# openSX70-dongle.net
KiCad netlist of a schematic drawn in EAGLE
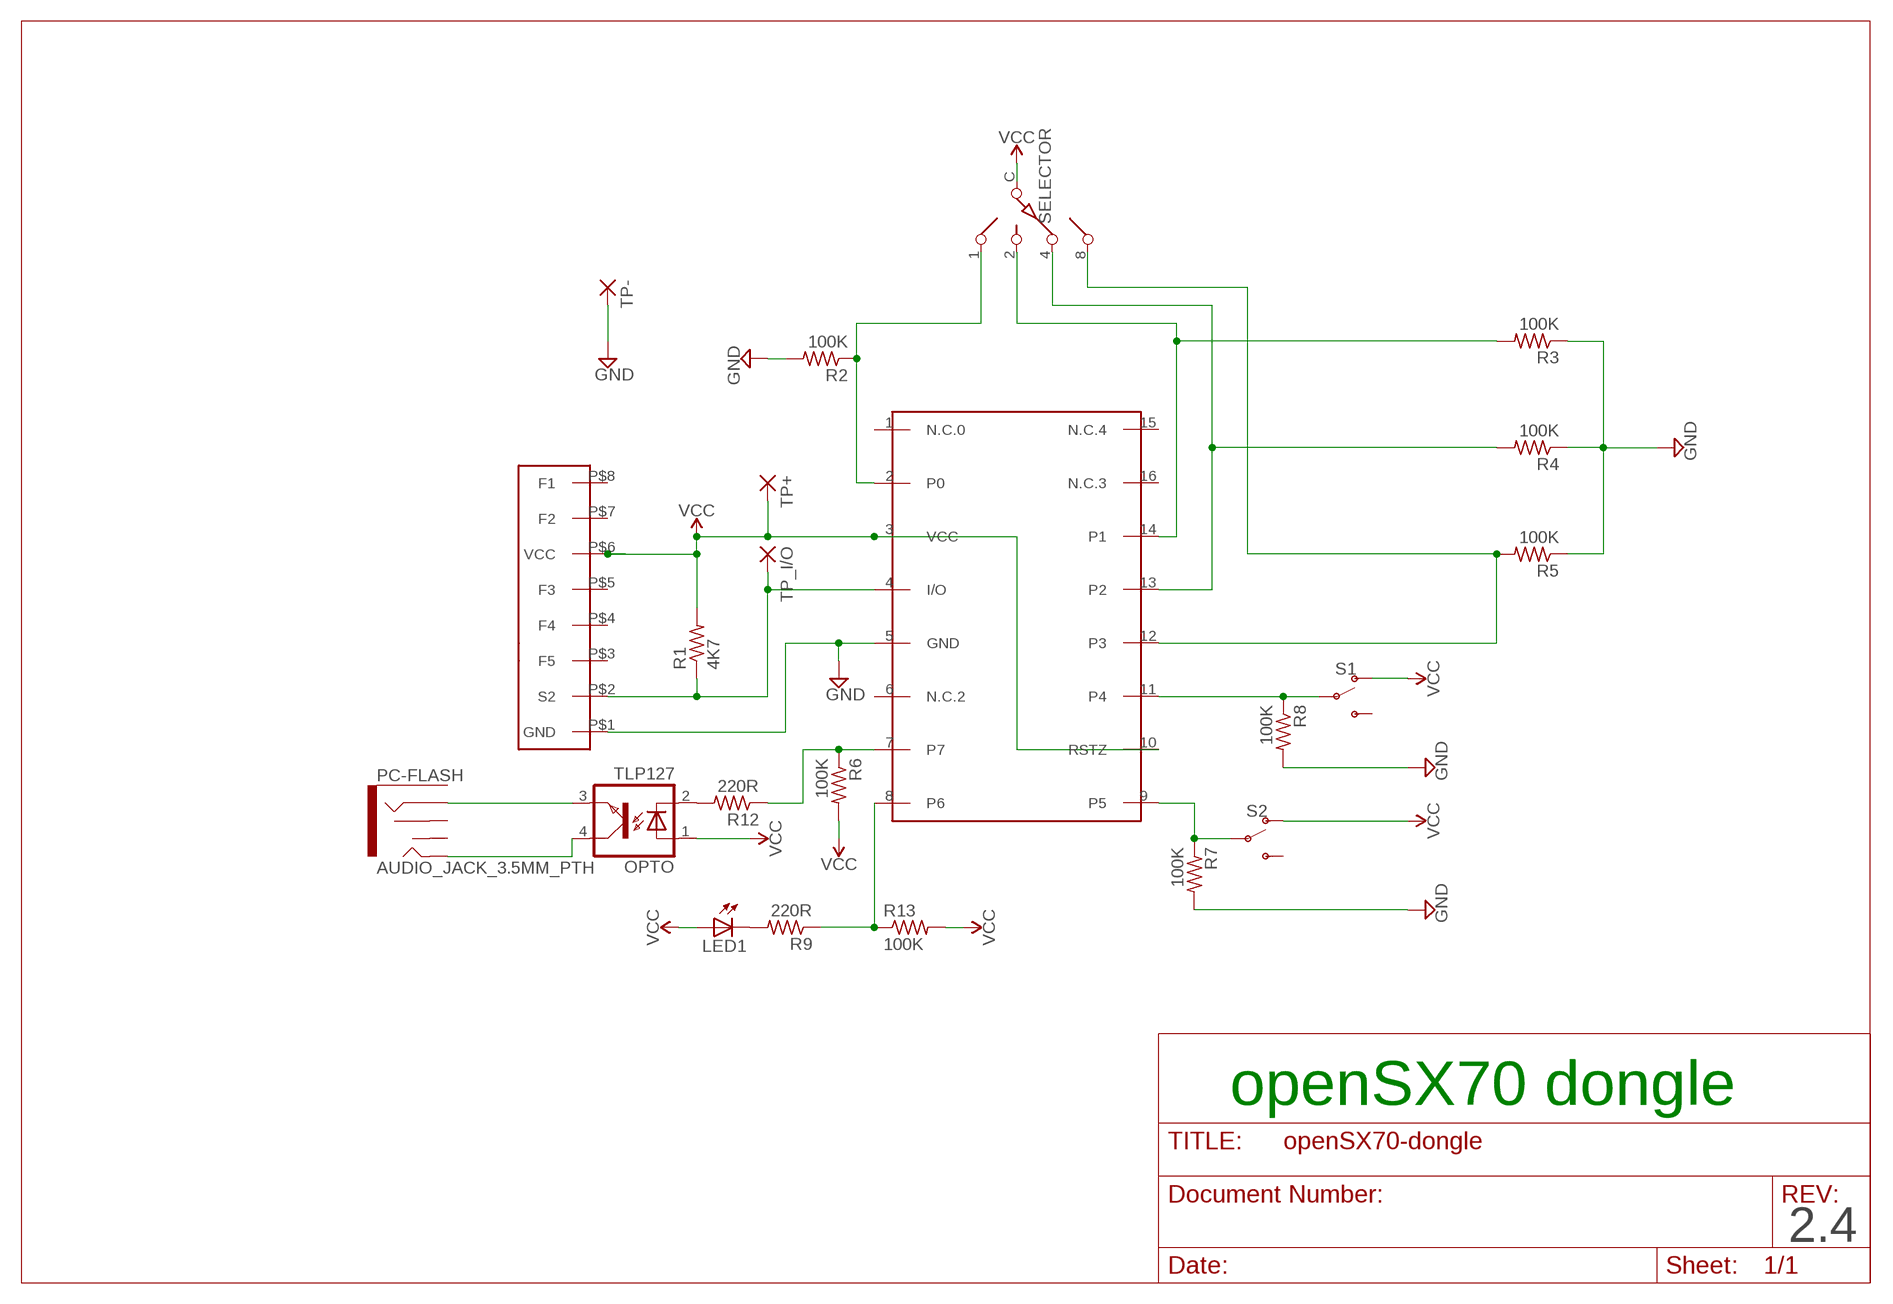
[diagram p0: schematic, sheet 1]

(export (version "E")
  (design (tool "Eeschema 10.0.6"))
  (components
    (comp (ref "DS2408")
      (value "DS2408")
      (footprint "eagle-import:SO16")
      (libsource (lib "eagle-import") (part "DS2408"))
    )
    (comp (ref "LED1")
      (value "LED3MM")
      (footprint "eagle-import:LED3MM")
      (libsource (lib "eagle-import") (part "LED3MM"))
    )
    (comp (ref "OPTO")
      (value "TLP127")
      (footprint "eagle-import:SO-4")
      (libsource (lib "eagle-import") (part "TLP127"))
    )
    (comp (ref "PC-FLASH")
      (value "AUDIO_JACK_3.5MM_PTH")
      (footprint "eagle-import:AUDIO-JACK")
      (libsource (lib "eagle-import") (part "AUDIO_JACK_3.5MM_PTH"))
    )
    (comp (ref "R1")
      (value "4K7")
      (footprint "eagle-import:M0805")
      (libsource (lib "eagle-import") (part "R-US_M0805"))
    )
    (comp (ref "R2")
      (value "100K")
      (footprint "eagle-import:M0805")
      (libsource (lib "eagle-import") (part "R-US_M0805"))
    )
    (comp (ref "R3")
      (value "100K")
      (footprint "eagle-import:M0805")
      (libsource (lib "eagle-import") (part "R-US_M0805"))
    )
    (comp (ref "R4")
      (value "100K")
      (footprint "eagle-import:M0805")
      (libsource (lib "eagle-import") (part "R-US_M0805"))
    )
    (comp (ref "R5")
      (value "100K")
      (footprint "eagle-import:M0805")
      (libsource (lib "eagle-import") (part "R-US_M0805"))
    )
    (comp (ref "R6")
      (value "100K")
      (footprint "eagle-import:M0805")
      (libsource (lib "eagle-import") (part "R-US_M0805"))
    )
    (comp (ref "R7")
      (value "100K")
      (footprint "eagle-import:M0805")
      (libsource (lib "eagle-import") (part "R-US_M0805"))
    )
    (comp (ref "R8")
      (value "100K")
      (footprint "eagle-import:M0805")
      (libsource (lib "eagle-import") (part "R-US_M0805"))
    )
    (comp (ref "R9")
      (value "220R")
      (footprint "eagle-import:M0805")
      (libsource (lib "eagle-import") (part "R-US_M0805"))
    )
    (comp (ref "R12")
      (value "220R")
      (footprint "eagle-import:M0805")
      (libsource (lib "eagle-import") (part "R-US_M0805"))
    )
    (comp (ref "R13")
      (value "100K")
      (footprint "eagle-import:M0805")
      (libsource (lib "eagle-import") (part "R-US_M0805"))
    )
    (comp (ref "S1")
      (value "SWITCH-SPDT-SMD-RIGHT-ANGLE")
      (footprint "eagle-import:SWITCH_SPST_SMD_A")
      (libsource (lib "eagle-import") (part "SWITCH-SPDT-SMD-RIGHT-ANGLE"))
    )
    (comp (ref "S2")
      (value "SWITCH-SPDT-SMD-RIGHT-ANGLE")
      (footprint "eagle-import:SWITCH_SPST_SMD_A")
      (libsource (lib "eagle-import") (part "SWITCH-SPDT-SMD-RIGHT-ANGLE"))
    )
    (comp (ref "SELECTOR")
      (value "SW-C16")
      (footprint "eagle-import:SW-C16")
      (libsource (lib "eagle-import") (part "SW-C16"))
    )
    (comp (ref "TP+")
      (value "SMD2")
      (footprint "eagle-import:SMD1,27-2,54")
      (libsource (lib "eagle-import") (part "SMD2"))
    )
    (comp (ref "TP-")
      (value "SMD2")
      (footprint "eagle-import:SMD1,27-2,54")
      (libsource (lib "eagle-import") (part "SMD2"))
    )
    (comp (ref "TP_I/O")
      (value "SMD2")
      (footprint "eagle-import:SMD1,27-2,54")
      (libsource (lib "eagle-import") (part "SMD2"))
    )
    (comp (ref "U$1")
      (value "FLASH-EDGE-CONNECTOR")
      (footprint "eagle-import:FLASH-EDGE-8")
      (libsource (lib "eagle-import") (part "FLASH-EDGE-CONNECTOR"))
    )
  )
  (nets
    (net (code "1") (name "GND") (class "Default")
      (node (ref "DS2408") (pin "5") (pinfunction "GND_5") (pintype "bidirectional"))
      (node (ref "R2") (pin "2") (pinfunction "2_2") (pintype "passive"))
      (node (ref "R3") (pin "1") (pinfunction "1_1") (pintype "passive"))
      (node (ref "R4") (pin "1") (pinfunction "1_1") (pintype "passive"))
      (node (ref "R5") (pin "1") (pinfunction "1_1") (pintype "passive"))
      (node (ref "R7") (pin "2") (pinfunction "2_2") (pintype "passive"))
      (node (ref "R8") (pin "2") (pinfunction "2_2") (pintype "passive"))
      (node (ref "TP-") (pin "1") (pinfunction "P_1") (pintype "passive"))
      (node (ref "U$1") (pin "P$1") (pinfunction "GND_P$1") (pintype "bidirectional"))
    )
    (net (code "2") (name "Net-(DS2408-I{slash}O)") (class "Default")
      (node (ref "DS2408") (pin "4") (pinfunction "I/O_4") (pintype "bidirectional"))
      (node (ref "R1") (pin "1") (pinfunction "1_1") (pintype "passive"))
      (node (ref "TP_I/O") (pin "1") (pinfunction "P_1") (pintype "passive"))
      (node (ref "U$1") (pin "P$2") (pinfunction "S2_P$2") (pintype "bidirectional"))
    )
    (net (code "3") (name "Net-(DS2408-P0)") (class "Default")
      (node (ref "DS2408") (pin "2") (pinfunction "P0_2") (pintype "bidirectional"))
      (node (ref "R2") (pin "1") (pinfunction "1_1") (pintype "passive"))
      (node (ref "SELECTOR") (pin "1") (pinfunction "1_1") (pintype "passive"))
    )
    (net (code "4") (name "Net-(DS2408-P1)") (class "Default")
      (node (ref "DS2408") (pin "14") (pinfunction "P1_14") (pintype "bidirectional"))
      (node (ref "R3") (pin "2") (pinfunction "2_2") (pintype "passive"))
      (node (ref "SELECTOR") (pin "2") (pinfunction "2_2") (pintype "passive"))
    )
    (net (code "5") (name "Net-(DS2408-P2)") (class "Default")
      (node (ref "DS2408") (pin "13") (pinfunction "P2_13") (pintype "bidirectional"))
      (node (ref "R4") (pin "2") (pinfunction "2_2") (pintype "passive"))
      (node (ref "SELECTOR") (pin "4") (pinfunction "4_4") (pintype "passive"))
    )
    (net (code "6") (name "Net-(DS2408-P3)") (class "Default")
      (node (ref "DS2408") (pin "12") (pinfunction "P3_12") (pintype "bidirectional"))
      (node (ref "R5") (pin "2") (pinfunction "2_2") (pintype "passive"))
      (node (ref "SELECTOR") (pin "8") (pinfunction "8_8") (pintype "passive"))
    )
    (net (code "7") (name "Net-(DS2408-P4)") (class "Default")
      (node (ref "DS2408") (pin "11") (pinfunction "P4_11") (pintype "bidirectional"))
      (node (ref "R8") (pin "1") (pinfunction "1_1") (pintype "passive"))
      (node (ref "S1") (pin "2") (pinfunction "P_2") (pintype "passive"))
    )
    (net (code "8") (name "Net-(DS2408-P5)") (class "Default")
      (node (ref "DS2408") (pin "9") (pinfunction "P5_9") (pintype "bidirectional"))
      (node (ref "R7") (pin "1") (pinfunction "1_1") (pintype "passive"))
      (node (ref "S2") (pin "2") (pinfunction "P_2") (pintype "passive"))
    )
    (net (code "9") (name "Net-(DS2408-P6)") (class "Default")
      (node (ref "DS2408") (pin "8") (pinfunction "P6_8") (pintype "bidirectional"))
      (node (ref "R13") (pin "1") (pinfunction "1_1") (pintype "passive"))
      (node (ref "R9") (pin "1") (pinfunction "1_1") (pintype "passive"))
    )
    (net (code "10") (name "Net-(DS2408-P7)") (class "Default")
      (node (ref "DS2408") (pin "7") (pinfunction "P7_7") (pintype "bidirectional"))
      (node (ref "R12") (pin "1") (pinfunction "1_1") (pintype "passive"))
      (node (ref "R6") (pin "1") (pinfunction "1_1") (pintype "passive"))
    )
    (net (code "11") (name "Net-(LED1-C)") (class "Default")
      (node (ref "LED1") (pin "K") (pinfunction "C_K") (pintype "passive"))
      (node (ref "R9") (pin "2") (pinfunction "2_2") (pintype "passive"))
    )
    (net (code "12") (name "Net-(OPTO-C)") (class "Default")
      (node (ref "OPTO") (pin "2") (pinfunction "C_2") (pintype "passive"))
      (node (ref "R12") (pin "2") (pinfunction "2_2") (pintype "passive"))
    )
    (net (code "13") (name "Net-(OPTO-COL)") (class "Default")
      (node (ref "OPTO") (pin "4") (pinfunction "COL_4") (pintype "passive"))
      (node (ref "PC-FLASH") (pin "TIP") (pinfunction "TIP_TIP") (pintype "bidirectional"))
    )
    (net (code "14") (name "Net-(OPTO-EMIT)") (class "Default")
      (node (ref "OPTO") (pin "3") (pinfunction "EMIT_3") (pintype "passive"))
      (node (ref "PC-FLASH") (pin "RING") (pinfunction "RING_RING") (pintype "bidirectional"))
    )
    (net (code "15") (name "VCC") (class "Default")
      (node (ref "DS2408") (pin "10") (pinfunction "RSTZ_10") (pintype "bidirectional"))
      (node (ref "DS2408") (pin "3") (pinfunction "VCC_3") (pintype "bidirectional"))
      (node (ref "LED1") (pin "A") (pinfunction "A_A") (pintype "passive"))
      (node (ref "OPTO") (pin "1") (pinfunction "A_1") (pintype "passive"))
      (node (ref "R1") (pin "2") (pinfunction "2_2") (pintype "passive"))
      (node (ref "R13") (pin "2") (pinfunction "2_2") (pintype "passive"))
      (node (ref "R6") (pin "2") (pinfunction "2_2") (pintype "passive"))
      (node (ref "S1") (pin "1") (pinfunction "O_1") (pintype "passive"))
      (node (ref "S2") (pin "1") (pinfunction "O_1") (pintype "passive"))
      (node (ref "SELECTOR") (pin "C") (pinfunction "C_C") (pintype "passive"))
      (node (ref "TP+") (pin "1") (pinfunction "P_1") (pintype "passive"))
      (node (ref "U$1") (pin "P$6") (pinfunction "VCC_P$6") (pintype "bidirectional"))
    )
    (net (code "16") (name "unconnected-(DS2408-N.C.0-Pad1)") (class "Default")
      (node (ref "DS2408") (pin "1") (pinfunction "N.C.0_1") (pintype "bidirectional"))
    )
    (net (code "17") (name "unconnected-(DS2408-N.C.2-Pad6)") (class "Default")
      (node (ref "DS2408") (pin "6") (pinfunction "N.C.2_6") (pintype "bidirectional"))
    )
    (net (code "18") (name "unconnected-(DS2408-N.C.3-Pad16)") (class "Default")
      (node (ref "DS2408") (pin "16") (pinfunction "N.C.3_16") (pintype "bidirectional"))
    )
    (net (code "19") (name "unconnected-(DS2408-N.C.4-Pad15)") (class "Default")
      (node (ref "DS2408") (pin "15") (pinfunction "N.C.4_15") (pintype "bidirectional"))
    )
    (net (code "20") (name "unconnected-(PC-FLASH-PadRSH)") (class "Default")
      (node (ref "PC-FLASH") (pin "RSH") (pinfunction "RSH_RSH") (pintype "bidirectional"))
    )
    (net (code "21") (name "unconnected-(PC-FLASH-PadSLEEVE)") (class "Default")
      (node (ref "PC-FLASH") (pin "SLEEVE") (pinfunction "SLEEVE_SLEEVE") (pintype "bidirectional"))
    )
    (net (code "22") (name "unconnected-(PC-FLASH-PadTSH)") (class "Default")
      (node (ref "PC-FLASH") (pin "TSH") (pinfunction "TSH_TSH") (pintype "bidirectional"))
    )
    (net (code "23") (name "unconnected-(S1-S-Pad3)") (class "Default")
      (node (ref "S1") (pin "3") (pinfunction "S_3") (pintype "passive"))
    )
    (net (code "24") (name "unconnected-(S2-S-Pad3)") (class "Default")
      (node (ref "S2") (pin "3") (pinfunction "S_3") (pintype "passive"))
    )
    (net (code "25") (name "unconnected-(U$1-F1-PadP$8)") (class "Default")
      (node (ref "U$1") (pin "P$8") (pinfunction "F1_P$8") (pintype "bidirectional"))
    )
    (net (code "26") (name "unconnected-(U$1-F2-PadP$7)") (class "Default")
      (node (ref "U$1") (pin "P$7") (pinfunction "F2_P$7") (pintype "bidirectional"))
    )
    (net (code "27") (name "unconnected-(U$1-F3-PadP$5)") (class "Default")
      (node (ref "U$1") (pin "P$5") (pinfunction "F3_P$5") (pintype "bidirectional"))
    )
    (net (code "28") (name "unconnected-(U$1-F4-PadP$4)") (class "Default")
      (node (ref "U$1") (pin "P$4") (pinfunction "F4_P$4") (pintype "bidirectional"))
    )
    (net (code "29") (name "unconnected-(U$1-F5-PadP$3)") (class "Default")
      (node (ref "U$1") (pin "P$3") (pinfunction "F5_P$3") (pintype "bidirectional"))
    )
  )
)
